# PT100.net
KiCad netlist of a schematic drawn in Altium Designer
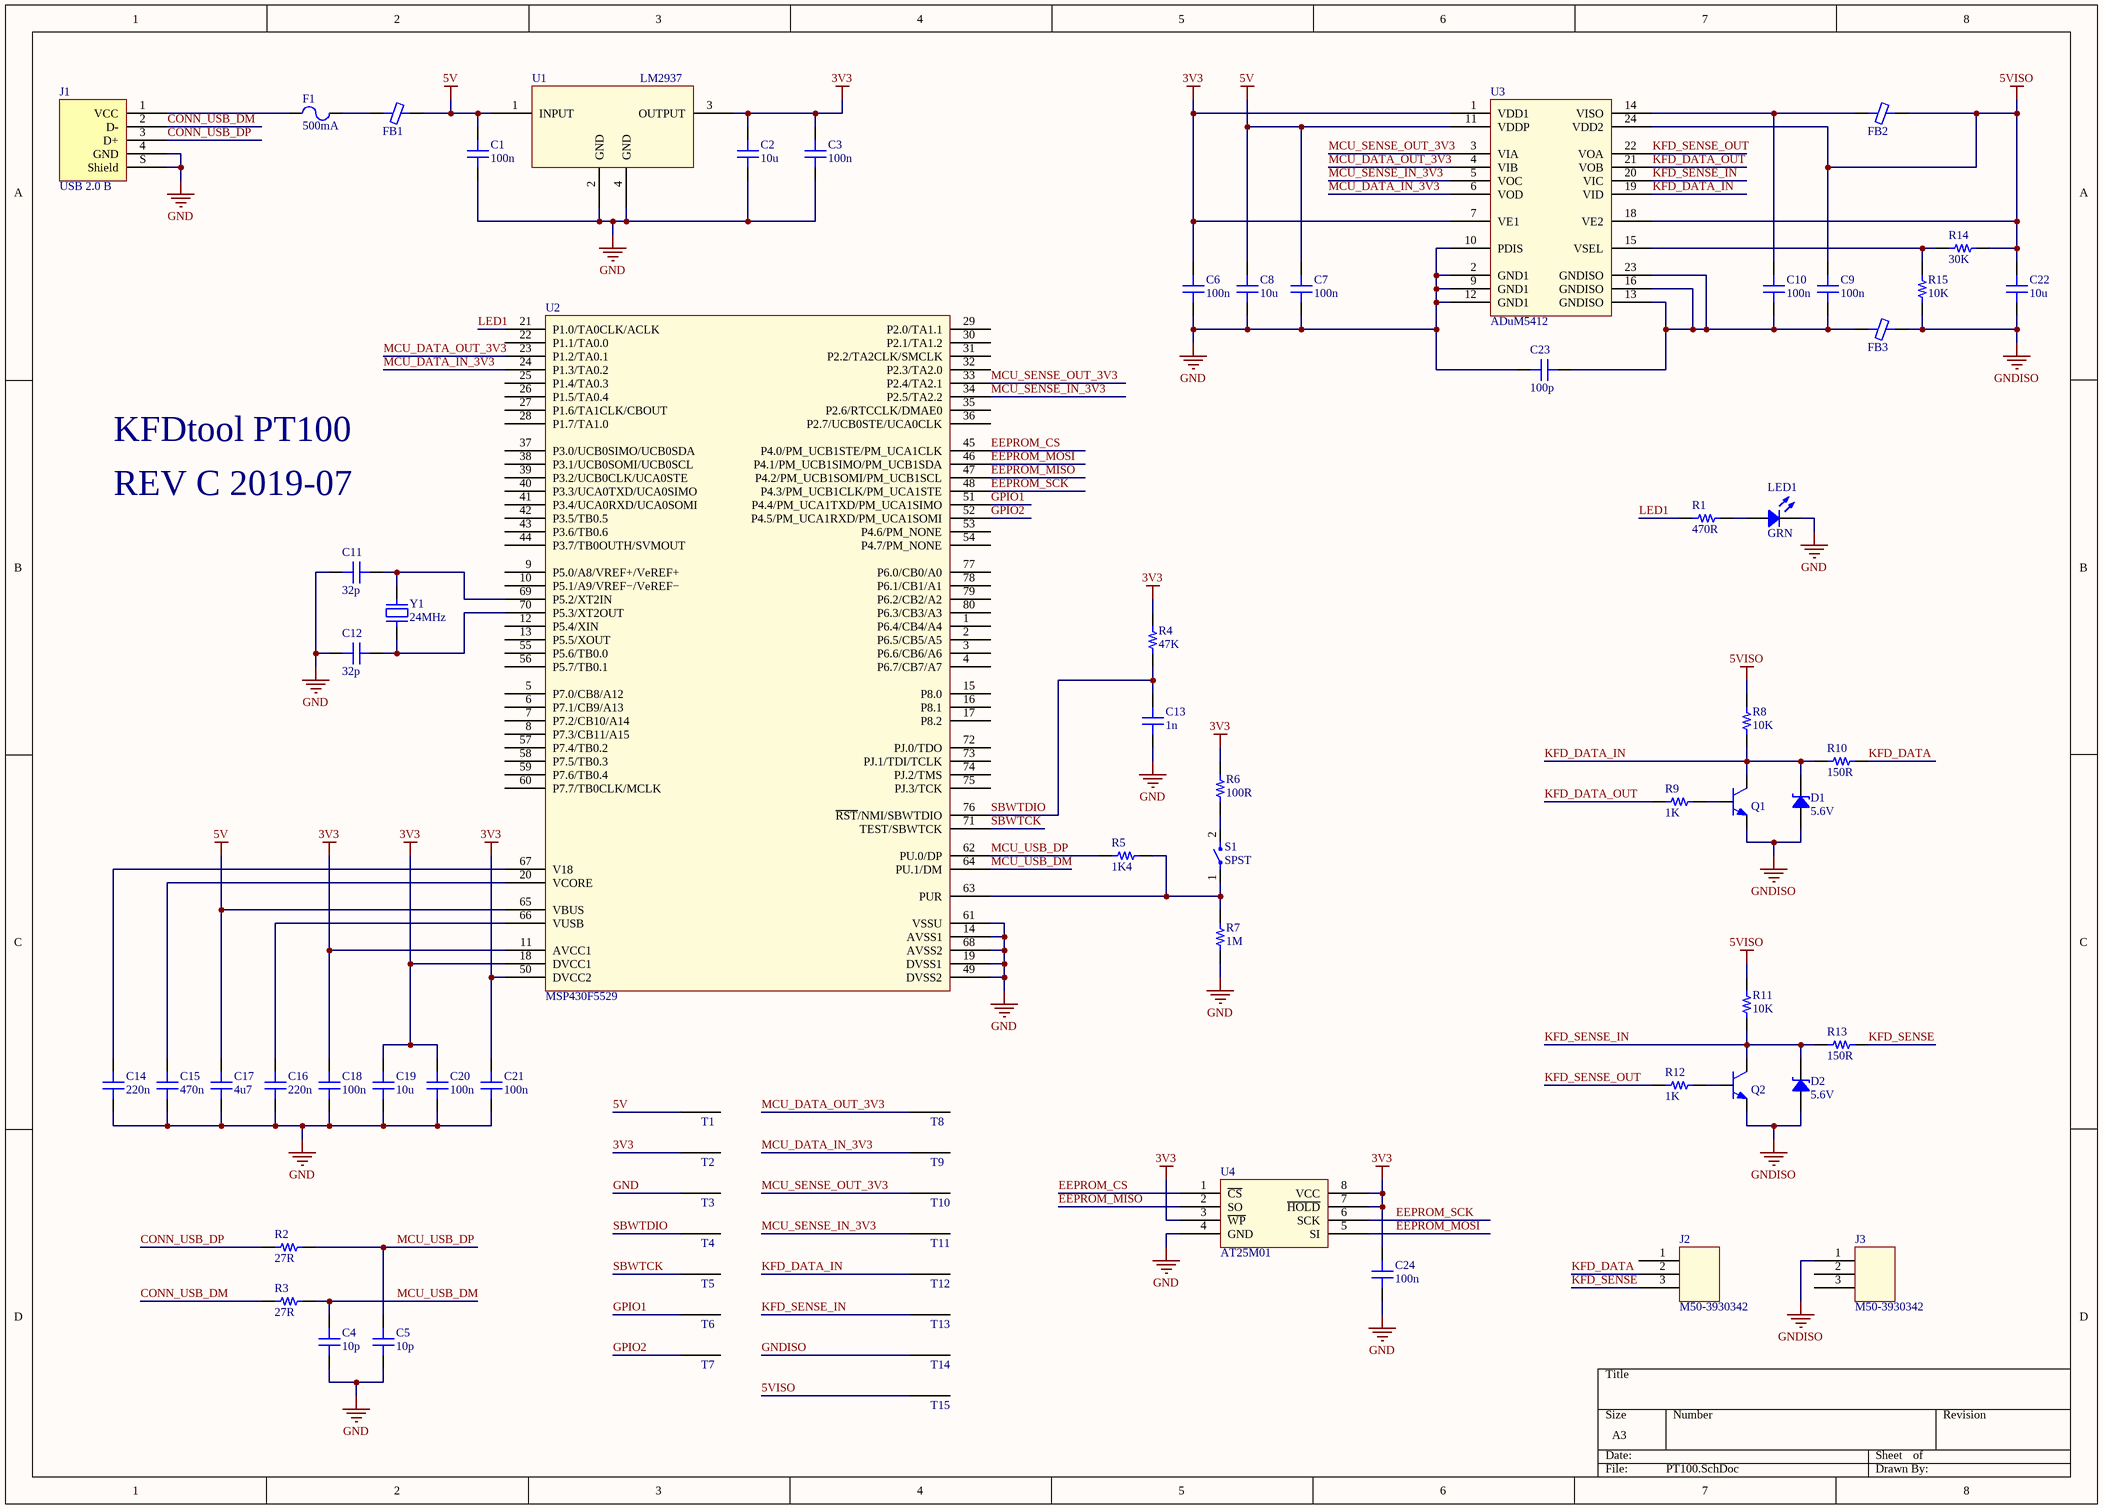
[diagram p0: PT100.SchDoc]

(export (version "E")
  (design (tool "Eeschema 10.0.6"))
  (components
    (comp (ref "C1")
      (value "100n")
      (footprint "CAP 0603")
      (libsource (lib "KFDtool Schematic Library") (part "Capacitor"))
    )
    (comp (ref "C2")
      (value "10u")
      (footprint "CAP 0603")
      (libsource (lib "KFDtool Schematic Library") (part "Capacitor"))
    )
    (comp (ref "C3")
      (value "100n")
      (footprint "CAP 0603")
      (libsource (lib "KFDtool Schematic Library") (part "Capacitor"))
    )
    (comp (ref "C4")
      (value "10p")
      (footprint "CAP 0603")
      (libsource (lib "KFDtool Schematic Library") (part "Capacitor"))
    )
    (comp (ref "C5")
      (value "10p")
      (footprint "CAP 0603")
      (libsource (lib "KFDtool Schematic Library") (part "Capacitor"))
    )
    (comp (ref "C6")
      (value "100n")
      (footprint "CAP 0603")
      (libsource (lib "KFDtool Schematic Library") (part "Capacitor"))
    )
    (comp (ref "C7")
      (value "100n")
      (footprint "CAP 0603")
      (libsource (lib "KFDtool Schematic Library") (part "Capacitor"))
    )
    (comp (ref "C8")
      (value "10u")
      (footprint "CAP 0603")
      (libsource (lib "KFDtool Schematic Library") (part "Capacitor"))
    )
    (comp (ref "C9")
      (value "100n")
      (footprint "CAP 0603")
      (libsource (lib "KFDtool Schematic Library") (part "Capacitor"))
    )
    (comp (ref "C10")
      (value "100n")
      (footprint "CAP 0603")
      (libsource (lib "KFDtool Schematic Library") (part "Capacitor"))
    )
    (comp (ref "C11")
      (value "32p")
      (footprint "CAP 0603")
      (libsource (lib "KFDtool Schematic Library") (part "Capacitor"))
    )
    (comp (ref "C12")
      (value "32p")
      (footprint "CAP 0603")
      (libsource (lib "KFDtool Schematic Library") (part "Capacitor"))
    )
    (comp (ref "C13")
      (value "1n")
      (footprint "CAP 0603")
      (libsource (lib "KFDtool Schematic Library") (part "Capacitor"))
    )
    (comp (ref "C14")
      (value "220n")
      (footprint "CAP 0603")
      (libsource (lib "KFDtool Schematic Library") (part "Capacitor"))
    )
    (comp (ref "C15")
      (value "470n")
      (footprint "CAP 0603")
      (libsource (lib "KFDtool Schematic Library") (part "Capacitor"))
    )
    (comp (ref "C16")
      (value "220n")
      (footprint "CAP 0603")
      (libsource (lib "KFDtool Schematic Library") (part "Capacitor"))
    )
    (comp (ref "C17")
      (value "4u7")
      (footprint "CAP 0603")
      (libsource (lib "KFDtool Schematic Library") (part "Capacitor"))
    )
    (comp (ref "C18")
      (value "100n")
      (footprint "CAP 0603")
      (libsource (lib "KFDtool Schematic Library") (part "Capacitor"))
    )
    (comp (ref "C19")
      (value "10u")
      (footprint "CAP 0603")
      (libsource (lib "KFDtool Schematic Library") (part "Capacitor"))
    )
    (comp (ref "C20")
      (value "100n")
      (footprint "CAP 0603")
      (libsource (lib "KFDtool Schematic Library") (part "Capacitor"))
    )
    (comp (ref "C21")
      (value "100n")
      (footprint "CAP 0603")
      (libsource (lib "KFDtool Schematic Library") (part "Capacitor"))
    )
    (comp (ref "C22")
      (value "10u")
      (footprint "CAP 0603")
      (libsource (lib "KFDtool Schematic Library") (part "Capacitor"))
    )
    (comp (ref "C23")
      (value "100p")
      (footprint "CAP 1812")
      (libsource (lib "KFDtool Schematic Library") (part "Capacitor"))
    )
    (comp (ref "C24")
      (value "100n")
      (footprint "CAP 0603")
      (libsource (lib "KFDtool Schematic Library") (part "Capacitor"))
    )
    (comp (ref "D1")
      (value "5.6V")
      (footprint "ON SEMI SOT-23-3")
      (libsource (lib "KFDtool Schematic Library") (part "Zener Diode"))
    )
    (comp (ref "D2")
      (value "5.6V")
      (footprint "ON SEMI SOT-23-3")
      (libsource (lib "KFDtool Schematic Library") (part "Zener Diode"))
    )
    (comp (ref "F1")
      (value "500mA")
      (footprint "PTC 2920")
      (libsource (lib "KFDtool Schematic Library") (part "PTC"))
    )
    (comp (ref "FB1")
      (value "Ferrite Chip")
      (footprint "CAP 0603")
      (libsource (lib "KFDtool Schematic Library") (part "Ferrite Chip"))
    )
    (comp (ref "FB2")
      (value "Ferrite Chip")
      (footprint "CAP 0603")
      (libsource (lib "KFDtool Schematic Library") (part "Ferrite Chip"))
    )
    (comp (ref "FB3")
      (value "Ferrite Chip")
      (footprint "CAP 0603")
      (libsource (lib "KFDtool Schematic Library") (part "Ferrite Chip"))
    )
    (comp (ref "J1")
      (value "USB 2.0 B")
      (footprint "FCI 61729-1011BLF")
      (libsource (lib "KFDtool Schematic Library") (part "FCI 61729-1011BLF"))
    )
    (comp (ref "J2")
      (value "M50-3930342")
      (footprint "HWN M50-3930342")
      (libsource (lib "KFDtool Schematic Library") (part "HWN M50-3930342"))
    )
    (comp (ref "J3")
      (value "M50-3930342")
      (footprint "HWN M50-3930342")
      (libsource (lib "KFDtool Schematic Library") (part "HWN M50-3930342"))
    )
    (comp (ref "LED1")
      (value "GRN")
      (footprint "KBRT WP934CB/GD")
      (libsource (lib "KFDtool Schematic Library") (part "LED"))
    )
    (comp (ref "Q1")
      (value "NPN Transistor")
      (footprint "ON SEMI SOT-23-3")
      (libsource (lib "KFDtool Schematic Library") (part "NPN Transistor"))
    )
    (comp (ref "Q2")
      (value "NPN Transistor")
      (footprint "ON SEMI SOT-23-3")
      (libsource (lib "KFDtool Schematic Library") (part "NPN Transistor"))
    )
    (comp (ref "R1")
      (value "470R")
      (footprint "RES 0603")
      (libsource (lib "KFDtool Schematic Library") (part "Resistor"))
    )
    (comp (ref "R2")
      (value "27R")
      (footprint "RES 0603")
      (libsource (lib "KFDtool Schematic Library") (part "Resistor"))
    )
    (comp (ref "R3")
      (value "27R")
      (footprint "RES 0603")
      (libsource (lib "KFDtool Schematic Library") (part "Resistor"))
    )
    (comp (ref "R4")
      (value "47K")
      (footprint "RES 0603")
      (libsource (lib "KFDtool Schematic Library") (part "Resistor"))
    )
    (comp (ref "R5")
      (value "1K4")
      (footprint "RES 0603")
      (libsource (lib "KFDtool Schematic Library") (part "Resistor"))
    )
    (comp (ref "R6")
      (value "100R")
      (footprint "RES 0603")
      (libsource (lib "KFDtool Schematic Library") (part "Resistor"))
    )
    (comp (ref "R7")
      (value "1M")
      (footprint "RES 0603")
      (libsource (lib "KFDtool Schematic Library") (part "Resistor"))
    )
    (comp (ref "R8")
      (value "10K")
      (footprint "RES 0603")
      (libsource (lib "KFDtool Schematic Library") (part "Resistor"))
    )
    (comp (ref "R9")
      (value "1K")
      (footprint "RES 0603")
      (libsource (lib "KFDtool Schematic Library") (part "Resistor"))
    )
    (comp (ref "R10")
      (value "150R")
      (footprint "RES 0603")
      (libsource (lib "KFDtool Schematic Library") (part "Resistor"))
    )
    (comp (ref "R11")
      (value "10K")
      (footprint "RES 0603")
      (libsource (lib "KFDtool Schematic Library") (part "Resistor"))
    )
    (comp (ref "R12")
      (value "1K")
      (footprint "RES 0603")
      (libsource (lib "KFDtool Schematic Library") (part "Resistor"))
    )
    (comp (ref "R13")
      (value "150R")
      (footprint "RES 0603")
      (libsource (lib "KFDtool Schematic Library") (part "Resistor"))
    )
    (comp (ref "R14")
      (value "30K")
      (footprint "RES 0603")
      (libsource (lib "KFDtool Schematic Library") (part "Resistor"))
    )
    (comp (ref "R15")
      (value "10K")
      (footprint "RES 0603")
      (libsource (lib "KFDtool Schematic Library") (part "Resistor"))
    )
    (comp (ref "S1")
      (value "SPST")
      (footprint "ESWI TL3340AF160QG")
      (libsource (lib "KFDtool Schematic Library") (part "SPST Switch"))
    )
    (comp (ref "T1")
      (value "Test Point")
      (footprint "TEST POINT")
      (libsource (lib "KFDtool Schematic Library") (part "Test Point"))
    )
    (comp (ref "T2")
      (value "Test Point")
      (footprint "TEST POINT")
      (libsource (lib "KFDtool Schematic Library") (part "Test Point"))
    )
    (comp (ref "T3")
      (value "Test Point")
      (footprint "TEST POINT")
      (libsource (lib "KFDtool Schematic Library") (part "Test Point"))
    )
    (comp (ref "T4")
      (value "Test Point")
      (footprint "TEST POINT")
      (libsource (lib "KFDtool Schematic Library") (part "Test Point"))
    )
    (comp (ref "T5")
      (value "Test Point")
      (footprint "TEST POINT")
      (libsource (lib "KFDtool Schematic Library") (part "Test Point"))
    )
    (comp (ref "T6")
      (value "Test Point")
      (footprint "TEST POINT")
      (libsource (lib "KFDtool Schematic Library") (part "Test Point"))
    )
    (comp (ref "T7")
      (value "Test Point")
      (footprint "TEST POINT")
      (libsource (lib "KFDtool Schematic Library") (part "Test Point"))
    )
    (comp (ref "T8")
      (value "Test Point")
      (footprint "TEST POINT")
      (libsource (lib "KFDtool Schematic Library") (part "Test Point"))
    )
    (comp (ref "T9")
      (value "Test Point")
      (footprint "TEST POINT")
      (libsource (lib "KFDtool Schematic Library") (part "Test Point"))
    )
    (comp (ref "T10")
      (value "Test Point")
      (footprint "TEST POINT")
      (libsource (lib "KFDtool Schematic Library") (part "Test Point"))
    )
    (comp (ref "T11")
      (value "Test Point")
      (footprint "TEST POINT")
      (libsource (lib "KFDtool Schematic Library") (part "Test Point"))
    )
    (comp (ref "T12")
      (value "Test Point")
      (footprint "TEST POINT")
      (libsource (lib "KFDtool Schematic Library") (part "Test Point"))
    )
    (comp (ref "T13")
      (value "Test Point")
      (footprint "TEST POINT")
      (libsource (lib "KFDtool Schematic Library") (part "Test Point"))
    )
    (comp (ref "T14")
      (value "Test Point")
      (footprint "TEST POINT")
      (libsource (lib "KFDtool Schematic Library") (part "Test Point"))
    )
    (comp (ref "T15")
      (value "Test Point")
      (footprint "TEST POINT")
      (libsource (lib "KFDtool Schematic Library") (part "Test Point"))
    )
    (comp (ref "U1")
      (value "LM2937")
      (footprint "TI LM2937IMP-3.3/NOPB")
      (libsource (lib "KFDtool Schematic Library") (part "TI LM2937"))
    )
    (comp (ref "U2")
      (value "MSP430F5529")
      (footprint "TI MSP430F5529IPNR")
      (libsource (lib "KFDtool Schematic Library") (part "TI MSP430F5529"))
    )
    (comp (ref "U3")
      (value "ADuM5412")
      (footprint "AD RS-24")
      (libsource (lib "KFDtool Schematic Library") (part "AD ADuM5412"))
    )
    (comp (ref "U4")
      (value "AT25M01")
      (footprint "ATML 8S1")
      (libsource (lib "KFDtool Schematic Library") (part "ATML AT25M01"))
    )
    (comp (ref "Y1")
      (value "24MHz")
      (footprint "ABRA ABLS2")
      (libsource (lib "KFDtool Schematic Library") (part "Crystal"))
    )
  )
  (nets
    (net (code "1") (name "/CONN_USB_DM") (class "Default")
      (node (ref "J1") (pin "2") (pinfunction "D-_2") (pintype "passive"))
      (node (ref "R3") (pin "1") (pinfunction "1_1") (pintype "passive"))
    )
    (net (code "2") (name "/CONN_USB_DP") (class "Default")
      (node (ref "J1") (pin "3") (pinfunction "D+_3") (pintype "passive"))
      (node (ref "R2") (pin "1") (pinfunction "1_1") (pintype "passive"))
    )
    (net (code "3") (name "/EEPROM_CS") (class "Default")
      (node (ref "U2") (pin "45") (pinfunction "P4.0/PM_UCB1STE/PM_UCA1CLK_45") (pintype "passive"))
      (node (ref "U4") (pin "1") (pinfunction "~{CS}_1") (pintype "passive"))
    )
    (net (code "4") (name "/EEPROM_MISO") (class "Default")
      (node (ref "U2") (pin "47") (pinfunction "P4.2/PM_UCB1SOMI/PM_UCB1SCL_47") (pintype "passive"))
      (node (ref "U4") (pin "2") (pinfunction "SO_2") (pintype "passive"))
    )
    (net (code "5") (name "/EEPROM_MOSI") (class "Default")
      (node (ref "U2") (pin "46") (pinfunction "P4.1/PM_UCB1SIMO/PM_UCB1SDA_46") (pintype "passive"))
      (node (ref "U4") (pin "5") (pinfunction "SI_5") (pintype "passive"))
    )
    (net (code "6") (name "/EEPROM_SCK") (class "Default")
      (node (ref "U2") (pin "48") (pinfunction "P4.3/PM_UCB1CLK/PM_UCA1STE_48") (pintype "passive"))
      (node (ref "U4") (pin "6") (pinfunction "SCK_6") (pintype "passive"))
    )
    (net (code "7") (name "/GPIO1") (class "Default")
      (node (ref "T6") (pin "1") (pinfunction "1_1") (pintype "passive"))
      (node (ref "U2") (pin "51") (pinfunction "P4.4/PM_UCA1TXD/PM_UCA1SIMO_51") (pintype "passive"))
    )
    (net (code "8") (name "/GPIO2") (class "Default")
      (node (ref "T7") (pin "1") (pinfunction "1_1") (pintype "passive"))
      (node (ref "U2") (pin "52") (pinfunction "P4.5/PM_UCA1RXD/PM_UCA1SOMI_52") (pintype "passive"))
    )
    (net (code "9") (name "/KFD_DATA") (class "Default")
      (node (ref "J2") (pin "2") (pinfunction "2_2") (pintype "passive"))
      (node (ref "R10") (pin "2") (pinfunction "2_2") (pintype "passive"))
    )
    (net (code "10") (name "/KFD_DATA_IN") (class "Default")
      (node (ref "D1") (pin "C") (pinfunction "C_C") (pintype "passive"))
      (node (ref "Q1") (pin "C") (pinfunction "C_C") (pintype "passive"))
      (node (ref "R10") (pin "1") (pinfunction "1_1") (pintype "passive"))
      (node (ref "R8") (pin "1") (pinfunction "1_1") (pintype "passive"))
      (node (ref "T12") (pin "1") (pinfunction "1_1") (pintype "passive"))
      (node (ref "U3") (pin "19") (pinfunction "VID_19") (pintype "passive"))
    )
    (net (code "11") (name "/KFD_DATA_OUT") (class "Default")
      (node (ref "R9") (pin "1") (pinfunction "1_1") (pintype "passive"))
      (node (ref "U3") (pin "21") (pinfunction "VOB_21") (pintype "passive"))
    )
    (net (code "12") (name "/KFD_SENSE") (class "Default")
      (node (ref "J2") (pin "3") (pinfunction "3_3") (pintype "passive"))
      (node (ref "R13") (pin "2") (pinfunction "2_2") (pintype "passive"))
    )
    (net (code "13") (name "/KFD_SENSE_IN") (class "Default")
      (node (ref "D2") (pin "C") (pinfunction "C_C") (pintype "passive"))
      (node (ref "Q2") (pin "C") (pinfunction "C_C") (pintype "passive"))
      (node (ref "R11") (pin "1") (pinfunction "1_1") (pintype "passive"))
      (node (ref "R13") (pin "1") (pinfunction "1_1") (pintype "passive"))
      (node (ref "T13") (pin "1") (pinfunction "1_1") (pintype "passive"))
      (node (ref "U3") (pin "20") (pinfunction "VIC_20") (pintype "passive"))
    )
    (net (code "14") (name "/KFD_SENSE_OUT") (class "Default")
      (node (ref "R12") (pin "1") (pinfunction "1_1") (pintype "passive"))
      (node (ref "U3") (pin "22") (pinfunction "VOA_22") (pintype "passive"))
    )
    (net (code "15") (name "/LED1") (class "Default")
      (node (ref "R1") (pin "1") (pinfunction "1_1") (pintype "passive"))
      (node (ref "U2") (pin "21") (pinfunction "P1.0/TA0CLK/ACLK_21") (pintype "passive"))
    )
    (net (code "16") (name "/MCU_DATA_IN_3V3") (class "Default")
      (node (ref "T9") (pin "1") (pinfunction "1_1") (pintype "passive"))
      (node (ref "U2") (pin "24") (pinfunction "P1.3/TA0.2_24") (pintype "passive"))
      (node (ref "U3") (pin "6") (pinfunction "VOD_6") (pintype "passive"))
    )
    (net (code "17") (name "/MCU_DATA_OUT_3V3") (class "Default")
      (node (ref "T8") (pin "1") (pinfunction "1_1") (pintype "passive"))
      (node (ref "U2") (pin "23") (pinfunction "P1.2/TA0.1_23") (pintype "passive"))
      (node (ref "U3") (pin "4") (pinfunction "VIB_4") (pintype "passive"))
    )
    (net (code "18") (name "/MCU_SENSE_IN_3V3") (class "Default")
      (node (ref "T11") (pin "1") (pinfunction "1_1") (pintype "passive"))
      (node (ref "U2") (pin "34") (pinfunction "P2.5/TA2.2_34") (pintype "passive"))
      (node (ref "U3") (pin "5") (pinfunction "VOC_5") (pintype "passive"))
    )
    (net (code "19") (name "/MCU_SENSE_OUT_3V3") (class "Default")
      (node (ref "T10") (pin "1") (pinfunction "1_1") (pintype "passive"))
      (node (ref "U2") (pin "33") (pinfunction "P2.4/TA2.1_33") (pintype "passive"))
      (node (ref "U3") (pin "3") (pinfunction "VIA_3") (pintype "passive"))
    )
    (net (code "20") (name "/MCU_USB_DM") (class "Default")
      (node (ref "C4") (pin "2") (pinfunction "2_2") (pintype "passive"))
      (node (ref "R3") (pin "2") (pinfunction "2_2") (pintype "passive"))
      (node (ref "U2") (pin "64") (pinfunction "PU.1/DM_64") (pintype "passive"))
    )
    (net (code "21") (name "/MCU_USB_DP") (class "Default")
      (node (ref "C5") (pin "2") (pinfunction "2_2") (pintype "passive"))
      (node (ref "R2") (pin "2") (pinfunction "2_2") (pintype "passive"))
      (node (ref "R5") (pin "1") (pinfunction "1_1") (pintype "passive"))
      (node (ref "U2") (pin "62") (pinfunction "PU.0/DP_62") (pintype "passive"))
    )
    (net (code "22") (name "/SBWTCK") (class "Default")
      (node (ref "T5") (pin "1") (pinfunction "1_1") (pintype "passive"))
      (node (ref "U2") (pin "71") (pinfunction "TEST/SBWTCK_71") (pintype "passive"))
    )
    (net (code "23") (name "/SBWTDIO") (class "Default")
      (node (ref "C13") (pin "2") (pinfunction "2_2") (pintype "passive"))
      (node (ref "R4") (pin "1") (pinfunction "1_1") (pintype "passive"))
      (node (ref "T4") (pin "1") (pinfunction "1_1") (pintype "passive"))
      (node (ref "U2") (pin "76") (pinfunction "~{RST}/NMI/SBWTDIO_76") (pintype "passive"))
    )
    (net (code "24") (name "3V3") (class "Default")
      (node (ref "C18") (pin "2") (pinfunction "2_2") (pintype "passive"))
      (node (ref "C19") (pin "2") (pinfunction "2_2") (pintype "passive"))
      (node (ref "C2") (pin "2") (pinfunction "2_2") (pintype "passive"))
      (node (ref "C20") (pin "2") (pinfunction "2_2") (pintype "passive"))
      (node (ref "C21") (pin "2") (pinfunction "2_2") (pintype "passive"))
      (node (ref "C24") (pin "2") (pinfunction "2_2") (pintype "passive"))
      (node (ref "C3") (pin "2") (pinfunction "2_2") (pintype "passive"))
      (node (ref "C6") (pin "2") (pinfunction "2_2") (pintype "passive"))
      (node (ref "R4") (pin "2") (pinfunction "2_2") (pintype "passive"))
      (node (ref "R6") (pin "2") (pinfunction "2_2") (pintype "passive"))
      (node (ref "T2") (pin "1") (pinfunction "1_1") (pintype "passive"))
      (node (ref "U1") (pin "3") (pinfunction "OUTPUT_3") (pintype "passive"))
      (node (ref "U2") (pin "11") (pinfunction "AVCC1_11") (pintype "passive"))
      (node (ref "U2") (pin "18") (pinfunction "DVCC1_18") (pintype "passive"))
      (node (ref "U2") (pin "50") (pinfunction "DVCC2_50") (pintype "passive"))
      (node (ref "U3") (pin "1") (pinfunction "VDD1_1") (pintype "passive"))
      (node (ref "U3") (pin "7") (pinfunction "VE1_7") (pintype "passive"))
      (node (ref "U4") (pin "3") (pinfunction "~{WP}_3") (pintype "passive"))
      (node (ref "U4") (pin "7") (pinfunction "~{HOLD}_7") (pintype "passive"))
      (node (ref "U4") (pin "8") (pinfunction "VCC_8") (pintype "passive"))
    )
    (net (code "25") (name "5V") (class "Default")
      (node (ref "C1") (pin "2") (pinfunction "2_2") (pintype "passive"))
      (node (ref "C17") (pin "2") (pinfunction "2_2") (pintype "passive"))
      (node (ref "C7") (pin "2") (pinfunction "2_2") (pintype "passive"))
      (node (ref "C8") (pin "2") (pinfunction "2_2") (pintype "passive"))
      (node (ref "FB1") (pin "2") (pinfunction "2_2") (pintype "passive"))
      (node (ref "T1") (pin "1") (pinfunction "1_1") (pintype "passive"))
      (node (ref "U1") (pin "1") (pinfunction "INPUT_1") (pintype "passive"))
      (node (ref "U2") (pin "65") (pinfunction "VBUS_65") (pintype "passive"))
      (node (ref "U3") (pin "11") (pinfunction "VDDP_11") (pintype "passive"))
    )
    (net (code "26") (name "5VISO") (class "Default")
      (node (ref "C22") (pin "2") (pinfunction "2_2") (pintype "passive"))
      (node (ref "C9") (pin "2") (pinfunction "2_2") (pintype "passive"))
      (node (ref "FB2") (pin "2") (pinfunction "2_2") (pintype "passive"))
      (node (ref "R11") (pin "2") (pinfunction "2_2") (pintype "passive"))
      (node (ref "R14") (pin "1") (pinfunction "1_1") (pintype "passive"))
      (node (ref "R8") (pin "2") (pinfunction "2_2") (pintype "passive"))
      (node (ref "T15") (pin "1") (pinfunction "1_1") (pintype "passive"))
      (node (ref "U3") (pin "18") (pinfunction "VE2_18") (pintype "passive"))
      (node (ref "U3") (pin "24") (pinfunction "VDD2_24") (pintype "passive"))
    )
    (net (code "27") (name "GND") (class "Default")
      (node (ref "C1") (pin "1") (pinfunction "1_1") (pintype "passive"))
      (node (ref "C11") (pin "1") (pinfunction "1_1") (pintype "passive"))
      (node (ref "C12") (pin "1") (pinfunction "1_1") (pintype "passive"))
      (node (ref "C13") (pin "1") (pinfunction "1_1") (pintype "passive"))
      (node (ref "C14") (pin "1") (pinfunction "1_1") (pintype "passive"))
      (node (ref "C15") (pin "1") (pinfunction "1_1") (pintype "passive"))
      (node (ref "C16") (pin "1") (pinfunction "1_1") (pintype "passive"))
      (node (ref "C17") (pin "1") (pinfunction "1_1") (pintype "passive"))
      (node (ref "C18") (pin "1") (pinfunction "1_1") (pintype "passive"))
      (node (ref "C19") (pin "1") (pinfunction "1_1") (pintype "passive"))
      (node (ref "C2") (pin "1") (pinfunction "1_1") (pintype "passive"))
      (node (ref "C20") (pin "1") (pinfunction "1_1") (pintype "passive"))
      (node (ref "C21") (pin "1") (pinfunction "1_1") (pintype "passive"))
      (node (ref "C23") (pin "1") (pinfunction "1_1") (pintype "passive"))
      (node (ref "C24") (pin "1") (pinfunction "1_1") (pintype "passive"))
      (node (ref "C3") (pin "1") (pinfunction "1_1") (pintype "passive"))
      (node (ref "C4") (pin "1") (pinfunction "1_1") (pintype "passive"))
      (node (ref "C5") (pin "1") (pinfunction "1_1") (pintype "passive"))
      (node (ref "C6") (pin "1") (pinfunction "1_1") (pintype "passive"))
      (node (ref "C7") (pin "1") (pinfunction "1_1") (pintype "passive"))
      (node (ref "C8") (pin "1") (pinfunction "1_1") (pintype "passive"))
      (node (ref "J1") (pin "4") (pinfunction "GND_4") (pintype "passive"))
      (node (ref "J1") (pin "S") (pinfunction "Shield_S") (pintype "passive"))
      (node (ref "LED1") (pin "2") (pinfunction "2_2") (pintype "passive"))
      (node (ref "R7") (pin "1") (pinfunction "1_1") (pintype "passive"))
      (node (ref "T3") (pin "1") (pinfunction "1_1") (pintype "passive"))
      (node (ref "U1") (pin "2") (pinfunction "GND_2") (pintype "passive"))
      (node (ref "U1") (pin "4") (pinfunction "GND_4") (pintype "passive"))
      (node (ref "U2") (pin "14") (pinfunction "AVSS1_14") (pintype "passive"))
      (node (ref "U2") (pin "19") (pinfunction "DVSS1_19") (pintype "passive"))
      (node (ref "U2") (pin "49") (pinfunction "DVSS2_49") (pintype "passive"))
      (node (ref "U2") (pin "61") (pinfunction "VSSU_61") (pintype "passive"))
      (node (ref "U2") (pin "68") (pinfunction "AVSS2_68") (pintype "passive"))
      (node (ref "U3") (pin "10") (pinfunction "PDIS_10") (pintype "passive"))
      (node (ref "U3") (pin "12") (pinfunction "GND1_12") (pintype "passive"))
      (node (ref "U3") (pin "2") (pinfunction "GND1_2") (pintype "passive"))
      (node (ref "U3") (pin "9") (pinfunction "GND1_9") (pintype "passive"))
      (node (ref "U4") (pin "4") (pinfunction "GND_4") (pintype "passive"))
    )
    (net (code "28") (name "GNDISO") (class "Default")
      (node (ref "C22") (pin "1") (pinfunction "1_1") (pintype "passive"))
      (node (ref "D1") (pin "A") (pinfunction "A_A") (pintype "passive"))
      (node (ref "D2") (pin "A") (pinfunction "A_A") (pintype "passive"))
      (node (ref "FB3") (pin "2") (pinfunction "2_2") (pintype "passive"))
      (node (ref "J3") (pin "1") (pinfunction "1_1") (pintype "passive"))
      (node (ref "Q1") (pin "E") (pinfunction "E_E") (pintype "passive"))
      (node (ref "Q2") (pin "E") (pinfunction "E_E") (pintype "passive"))
      (node (ref "R15") (pin "1") (pinfunction "1_1") (pintype "passive"))
      (node (ref "T14") (pin "1") (pinfunction "1_1") (pintype "passive"))
    )
    (net (code "29") (name "Net-(C10-Pad1)") (class "Default")
      (node (ref "C10") (pin "1") (pinfunction "1_1") (pintype "passive"))
      (node (ref "C23") (pin "2") (pinfunction "2_2") (pintype "passive"))
      (node (ref "C9") (pin "1") (pinfunction "1_1") (pintype "passive"))
      (node (ref "FB3") (pin "1") (pinfunction "1_1") (pintype "passive"))
      (node (ref "U3") (pin "13") (pinfunction "GNDISO_13") (pintype "passive"))
      (node (ref "U3") (pin "16") (pinfunction "GNDISO_16") (pintype "passive"))
      (node (ref "U3") (pin "23") (pinfunction "GNDISO_23") (pintype "passive"))
    )
    (net (code "30") (name "Net-(F1-Pad2)") (class "Default")
      (node (ref "F1") (pin "2") (pinfunction "2_2") (pintype "passive"))
      (node (ref "FB1") (pin "1") (pinfunction "1_1") (pintype "passive"))
    )
    (net (code "31") (name "Net-(J1-VCC)") (class "Default")
      (node (ref "F1") (pin "1") (pinfunction "1_1") (pintype "passive"))
      (node (ref "J1") (pin "1") (pinfunction "VCC_1") (pintype "passive"))
    )
    (net (code "32") (name "Net-(LED1-Pad1)") (class "Default")
      (node (ref "LED1") (pin "1") (pinfunction "1_1") (pintype "passive"))
      (node (ref "R1") (pin "2") (pinfunction "2_2") (pintype "passive"))
    )
    (net (code "33") (name "Net-(Q1-PadB)") (class "Default")
      (node (ref "Q1") (pin "B") (pinfunction "B_B") (pintype "passive"))
      (node (ref "R9") (pin "2") (pinfunction "2_2") (pintype "passive"))
    )
    (net (code "34") (name "Net-(Q2-PadB)") (class "Default")
      (node (ref "Q2") (pin "B") (pinfunction "B_B") (pintype "passive"))
      (node (ref "R12") (pin "2") (pinfunction "2_2") (pintype "passive"))
    )
    (net (code "35") (name "Net-(R6-Pad1)") (class "Default")
      (node (ref "R6") (pin "1") (pinfunction "1_1") (pintype "passive"))
      (node (ref "S1") (pin "2") (pinfunction "2_2") (pintype "passive"))
    )
    (net (code "36") (name "Net-(U2-P5.2{slash}XT2IN)") (class "Default")
      (node (ref "C11") (pin "2") (pinfunction "2_2") (pintype "passive"))
      (node (ref "U2") (pin "69") (pinfunction "P5.2/XT2IN_69") (pintype "passive"))
      (node (ref "Y1") (pin "2") (pinfunction "2_2") (pintype "passive"))
    )
    (net (code "37") (name "Net-(U2-P5.3{slash}XT2OUT)") (class "Default")
      (node (ref "C12") (pin "2") (pinfunction "2_2") (pintype "passive"))
      (node (ref "U2") (pin "70") (pinfunction "P5.3/XT2OUT_70") (pintype "passive"))
      (node (ref "Y1") (pin "1") (pinfunction "1_1") (pintype "passive"))
    )
    (net (code "38") (name "Net-(U2-PUR)") (class "Default")
      (node (ref "R5") (pin "2") (pinfunction "2_2") (pintype "passive"))
      (node (ref "R7") (pin "2") (pinfunction "2_2") (pintype "passive"))
      (node (ref "S1") (pin "1") (pinfunction "1_1") (pintype "passive"))
      (node (ref "U2") (pin "63") (pinfunction "PUR_63") (pintype "passive"))
    )
    (net (code "39") (name "Net-(U2-V18)") (class "Default")
      (node (ref "C14") (pin "2") (pinfunction "2_2") (pintype "passive"))
      (node (ref "U2") (pin "67") (pinfunction "V18_67") (pintype "passive"))
    )
    (net (code "40") (name "Net-(U2-VCORE)") (class "Default")
      (node (ref "C15") (pin "2") (pinfunction "2_2") (pintype "passive"))
      (node (ref "U2") (pin "20") (pinfunction "VCORE_20") (pintype "passive"))
    )
    (net (code "41") (name "Net-(U2-VUSB)") (class "Default")
      (node (ref "C16") (pin "2") (pinfunction "2_2") (pintype "passive"))
      (node (ref "U2") (pin "66") (pinfunction "VUSB_66") (pintype "passive"))
    )
    (net (code "42") (name "Net-(U3-VISO)") (class "Default")
      (node (ref "C10") (pin "2") (pinfunction "2_2") (pintype "passive"))
      (node (ref "FB2") (pin "1") (pinfunction "1_1") (pintype "passive"))
      (node (ref "U3") (pin "14") (pinfunction "VISO_14") (pintype "passive"))
    )
    (net (code "43") (name "Net-(U3-VSEL)") (class "Default")
      (node (ref "R14") (pin "2") (pinfunction "2_2") (pintype "passive"))
      (node (ref "R15") (pin "2") (pinfunction "2_2") (pintype "passive"))
      (node (ref "U3") (pin "15") (pinfunction "VSEL_15") (pintype "passive"))
    )
    (net (code "44") (name "unconnected-(J2-Pad1)") (class "Default")
      (node (ref "J2") (pin "1") (pinfunction "1_1") (pintype "passive"))
    )
    (net (code "45") (name "unconnected-(J3-Pad2)") (class "Default")
      (node (ref "J3") (pin "2") (pinfunction "2_2") (pintype "passive"))
    )
    (net (code "46") (name "unconnected-(J3-Pad3)") (class "Default")
      (node (ref "J3") (pin "3") (pinfunction "3_3") (pintype "passive"))
    )
    (net (code "47") (name "unconnected-(U2-P1.1{slash}TA0.0-Pad22)") (class "Default")
      (node (ref "U2") (pin "22") (pinfunction "P1.1/TA0.0_22") (pintype "passive"))
    )
    (net (code "48") (name "unconnected-(U2-P1.4{slash}TA0.3-Pad25)") (class "Default")
      (node (ref "U2") (pin "25") (pinfunction "P1.4/TA0.3_25") (pintype "passive"))
    )
    (net (code "49") (name "unconnected-(U2-P1.5{slash}TA0.4-Pad26)") (class "Default")
      (node (ref "U2") (pin "26") (pinfunction "P1.5/TA0.4_26") (pintype "passive"))
    )
    (net (code "50") (name "unconnected-(U2-P1.6{slash}TA1CLK{slash}CBOUT-Pad27)") (class "Default")
      (node (ref "U2") (pin "27") (pinfunction "P1.6/TA1CLK/CBOUT_27") (pintype "passive"))
    )
    (net (code "51") (name "unconnected-(U2-P1.7{slash}TA1.0-Pad28)") (class "Default")
      (node (ref "U2") (pin "28") (pinfunction "P1.7/TA1.0_28") (pintype "passive"))
    )
    (net (code "52") (name "unconnected-(U2-P2.0{slash}TA1.1-Pad29)") (class "Default")
      (node (ref "U2") (pin "29") (pinfunction "P2.0/TA1.1_29") (pintype "passive"))
    )
    (net (code "53") (name "unconnected-(U2-P2.1{slash}TA1.2-Pad30)") (class "Default")
      (node (ref "U2") (pin "30") (pinfunction "P2.1/TA1.2_30") (pintype "passive"))
    )
    (net (code "54") (name "unconnected-(U2-P2.2{slash}TA2CLK{slash}SMCLK-Pad31)") (class "Default")
      (node (ref "U2") (pin "31") (pinfunction "P2.2/TA2CLK/SMCLK_31") (pintype "passive"))
    )
    (net (code "55") (name "unconnected-(U2-P2.3{slash}TA2.0-Pad32)") (class "Default")
      (node (ref "U2") (pin "32") (pinfunction "P2.3/TA2.0_32") (pintype "passive"))
    )
    (net (code "56") (name "unconnected-(U2-P2.6{slash}RTCCLK{slash}DMAE0-Pad35)") (class "Default")
      (node (ref "U2") (pin "35") (pinfunction "P2.6/RTCCLK/DMAE0_35") (pintype "passive"))
    )
    (net (code "57") (name "unconnected-(U2-P2.7{slash}UCB0STE{slash}UCA0CLK-Pad36)") (class "Default")
      (node (ref "U2") (pin "36") (pinfunction "P2.7/UCB0STE/UCA0CLK_36") (pintype "passive"))
    )
    (net (code "58") (name "unconnected-(U2-P3.0{slash}UCB0SIMO{slash}UCB0SDA-Pad37)") (class "Default")
      (node (ref "U2") (pin "37") (pinfunction "P3.0/UCB0SIMO/UCB0SDA_37") (pintype "passive"))
    )
    (net (code "59") (name "unconnected-(U2-P3.1{slash}UCB0SOMI{slash}UCB0SCL-Pad38)") (class "Default")
      (node (ref "U2") (pin "38") (pinfunction "P3.1/UCB0SOMI/UCB0SCL_38") (pintype "passive"))
    )
    (net (code "60") (name "unconnected-(U2-P3.2{slash}UCB0CLK{slash}UCA0STE-Pad39)") (class "Default")
      (node (ref "U2") (pin "39") (pinfunction "P3.2/UCB0CLK/UCA0STE_39") (pintype "passive"))
    )
    (net (code "61") (name "unconnected-(U2-P3.3{slash}UCA0TXD{slash}UCA0SIMO-Pad40)") (class "Default")
      (node (ref "U2") (pin "40") (pinfunction "P3.3/UCA0TXD/UCA0SIMO_40") (pintype "passive"))
    )
    (net (code "62") (name "unconnected-(U2-P3.4{slash}UCA0RXD{slash}UCA0SOMI-Pad41)") (class "Default")
      (node (ref "U2") (pin "41") (pinfunction "P3.4/UCA0RXD/UCA0SOMI_41") (pintype "passive"))
    )
    (net (code "63") (name "unconnected-(U2-P3.5{slash}TB0.5-Pad42)") (class "Default")
      (node (ref "U2") (pin "42") (pinfunction "P3.5/TB0.5_42") (pintype "passive"))
    )
    (net (code "64") (name "unconnected-(U2-P3.6{slash}TB0.6-Pad43)") (class "Default")
      (node (ref "U2") (pin "43") (pinfunction "P3.6/TB0.6_43") (pintype "passive"))
    )
    (net (code "65") (name "unconnected-(U2-P3.7{slash}TB0OUTH{slash}SVMOUT-Pad44)") (class "Default")
      (node (ref "U2") (pin "44") (pinfunction "P3.7/TB0OUTH/SVMOUT_44") (pintype "passive"))
    )
    (net (code "66") (name "unconnected-(U2-P4.6{slash}PM_NONE-Pad53)") (class "Default")
      (node (ref "U2") (pin "53") (pinfunction "P4.6/PM_NONE_53") (pintype "passive"))
    )
    (net (code "67") (name "unconnected-(U2-P4.7{slash}PM_NONE-Pad54)") (class "Default")
      (node (ref "U2") (pin "54") (pinfunction "P4.7/PM_NONE_54") (pintype "passive"))
    )
    (net (code "68") (name "unconnected-(U2-P5.0{slash}A8{slash}VREF+{slash}VeREF+-Pad9)") (class "Default")
      (node (ref "U2") (pin "9") (pinfunction "P5.0/A8/VREF+/VeREF+_9") (pintype "passive"))
    )
    (net (code "69") (name "unconnected-(U2-P5.1{slash}A9{slash}VREF−{slash}VeREF−-Pad10)") (class "Default")
      (node (ref "U2") (pin "10") (pinfunction "P5.1/A9/VREF−/VeREF−_10") (pintype "passive"))
    )
    (net (code "70") (name "unconnected-(U2-P5.4{slash}XIN-Pad12)") (class "Default")
      (node (ref "U2") (pin "12") (pinfunction "P5.4/XIN_12") (pintype "passive"))
    )
    (net (code "71") (name "unconnected-(U2-P5.5{slash}XOUT-Pad13)") (class "Default")
      (node (ref "U2") (pin "13") (pinfunction "P5.5/XOUT_13") (pintype "passive"))
    )
    (net (code "72") (name "unconnected-(U2-P5.6{slash}TB0.0-Pad55)") (class "Default")
      (node (ref "U2") (pin "55") (pinfunction "P5.6/TB0.0_55") (pintype "passive"))
    )
    (net (code "73") (name "unconnected-(U2-P5.7{slash}TB0.1-Pad56)") (class "Default")
      (node (ref "U2") (pin "56") (pinfunction "P5.7/TB0.1_56") (pintype "passive"))
    )
    (net (code "74") (name "unconnected-(U2-P6.0{slash}CB0{slash}A0-Pad77)") (class "Default")
      (node (ref "U2") (pin "77") (pinfunction "P6.0/CB0/A0_77") (pintype "passive"))
    )
    (net (code "75") (name "unconnected-(U2-P6.1{slash}CB1{slash}A1-Pad78)") (class "Default")
      (node (ref "U2") (pin "78") (pinfunction "P6.1/CB1/A1_78") (pintype "passive"))
    )
    (net (code "76") (name "unconnected-(U2-P6.2{slash}CB2{slash}A2-Pad79)") (class "Default")
      (node (ref "U2") (pin "79") (pinfunction "P6.2/CB2/A2_79") (pintype "passive"))
    )
    (net (code "77") (name "unconnected-(U2-P6.3{slash}CB3{slash}A3-Pad80)") (class "Default")
      (node (ref "U2") (pin "80") (pinfunction "P6.3/CB3/A3_80") (pintype "passive"))
    )
    (net (code "78") (name "unconnected-(U2-P6.4{slash}CB4{slash}A4-Pad1)") (class "Default")
      (node (ref "U2") (pin "1") (pinfunction "P6.4/CB4/A4_1") (pintype "passive"))
    )
    (net (code "79") (name "unconnected-(U2-P6.5{slash}CB5{slash}A5-Pad2)") (class "Default")
      (node (ref "U2") (pin "2") (pinfunction "P6.5/CB5/A5_2") (pintype "passive"))
    )
    (net (code "80") (name "unconnected-(U2-P6.6{slash}CB6{slash}A6-Pad3)") (class "Default")
      (node (ref "U2") (pin "3") (pinfunction "P6.6/CB6/A6_3") (pintype "passive"))
    )
    (net (code "81") (name "unconnected-(U2-P6.7{slash}CB7{slash}A7-Pad4)") (class "Default")
      (node (ref "U2") (pin "4") (pinfunction "P6.7/CB7/A7_4") (pintype "passive"))
    )
    (net (code "82") (name "unconnected-(U2-P7.0{slash}CB8{slash}A12-Pad5)") (class "Default")
      (node (ref "U2") (pin "5") (pinfunction "P7.0/CB8/A12_5") (pintype "passive"))
    )
    (net (code "83") (name "unconnected-(U2-P7.1{slash}CB9{slash}A13-Pad6)") (class "Default")
      (node (ref "U2") (pin "6") (pinfunction "P7.1/CB9/A13_6") (pintype "passive"))
    )
    (net (code "84") (name "unconnected-(U2-P7.2{slash}CB10{slash}A14-Pad7)") (class "Default")
      (node (ref "U2") (pin "7") (pinfunction "P7.2/CB10/A14_7") (pintype "passive"))
    )
    (net (code "85") (name "unconnected-(U2-P7.3{slash}CB11{slash}A15-Pad8)") (class "Default")
      (node (ref "U2") (pin "8") (pinfunction "P7.3/CB11/A15_8") (pintype "passive"))
    )
    (net (code "86") (name "unconnected-(U2-P7.4{slash}TB0.2-Pad57)") (class "Default")
      (node (ref "U2") (pin "57") (pinfunction "P7.4/TB0.2_57") (pintype "passive"))
    )
    (net (code "87") (name "unconnected-(U2-P7.5{slash}TB0.3-Pad58)") (class "Default")
      (node (ref "U2") (pin "58") (pinfunction "P7.5/TB0.3_58") (pintype "passive"))
    )
    (net (code "88") (name "unconnected-(U2-P7.6{slash}TB0.4-Pad59)") (class "Default")
      (node (ref "U2") (pin "59") (pinfunction "P7.6/TB0.4_59") (pintype "passive"))
    )
    (net (code "89") (name "unconnected-(U2-P7.7{slash}TB0CLK{slash}MCLK-Pad60)") (class "Default")
      (node (ref "U2") (pin "60") (pinfunction "P7.7/TB0CLK/MCLK_60") (pintype "passive"))
    )
    (net (code "90") (name "unconnected-(U2-P8.0-Pad15)") (class "Default")
      (node (ref "U2") (pin "15") (pinfunction "P8.0_15") (pintype "passive"))
    )
    (net (code "91") (name "unconnected-(U2-P8.1-Pad16)") (class "Default")
      (node (ref "U2") (pin "16") (pinfunction "P8.1_16") (pintype "passive"))
    )
    (net (code "92") (name "unconnected-(U2-P8.2-Pad17)") (class "Default")
      (node (ref "U2") (pin "17") (pinfunction "P8.2_17") (pintype "passive"))
    )
    (net (code "93") (name "unconnected-(U2-PJ.0{slash}TDO-Pad72)") (class "Default")
      (node (ref "U2") (pin "72") (pinfunction "PJ.0/TDO_72") (pintype "passive"))
    )
    (net (code "94") (name "unconnected-(U2-PJ.1{slash}TDI{slash}TCLK-Pad73)") (class "Default")
      (node (ref "U2") (pin "73") (pinfunction "PJ.1/TDI/TCLK_73") (pintype "passive"))
    )
    (net (code "95") (name "unconnected-(U2-PJ.2{slash}TMS-Pad74)") (class "Default")
      (node (ref "U2") (pin "74") (pinfunction "PJ.2/TMS_74") (pintype "passive"))
    )
    (net (code "96") (name "unconnected-(U2-PJ.3{slash}TCK-Pad75)") (class "Default")
      (node (ref "U2") (pin "75") (pinfunction "PJ.3/TCK_75") (pintype "passive"))
    )
  )
)
